# SFP.net
KiCad netlist of a schematic drawn in Altium Designer
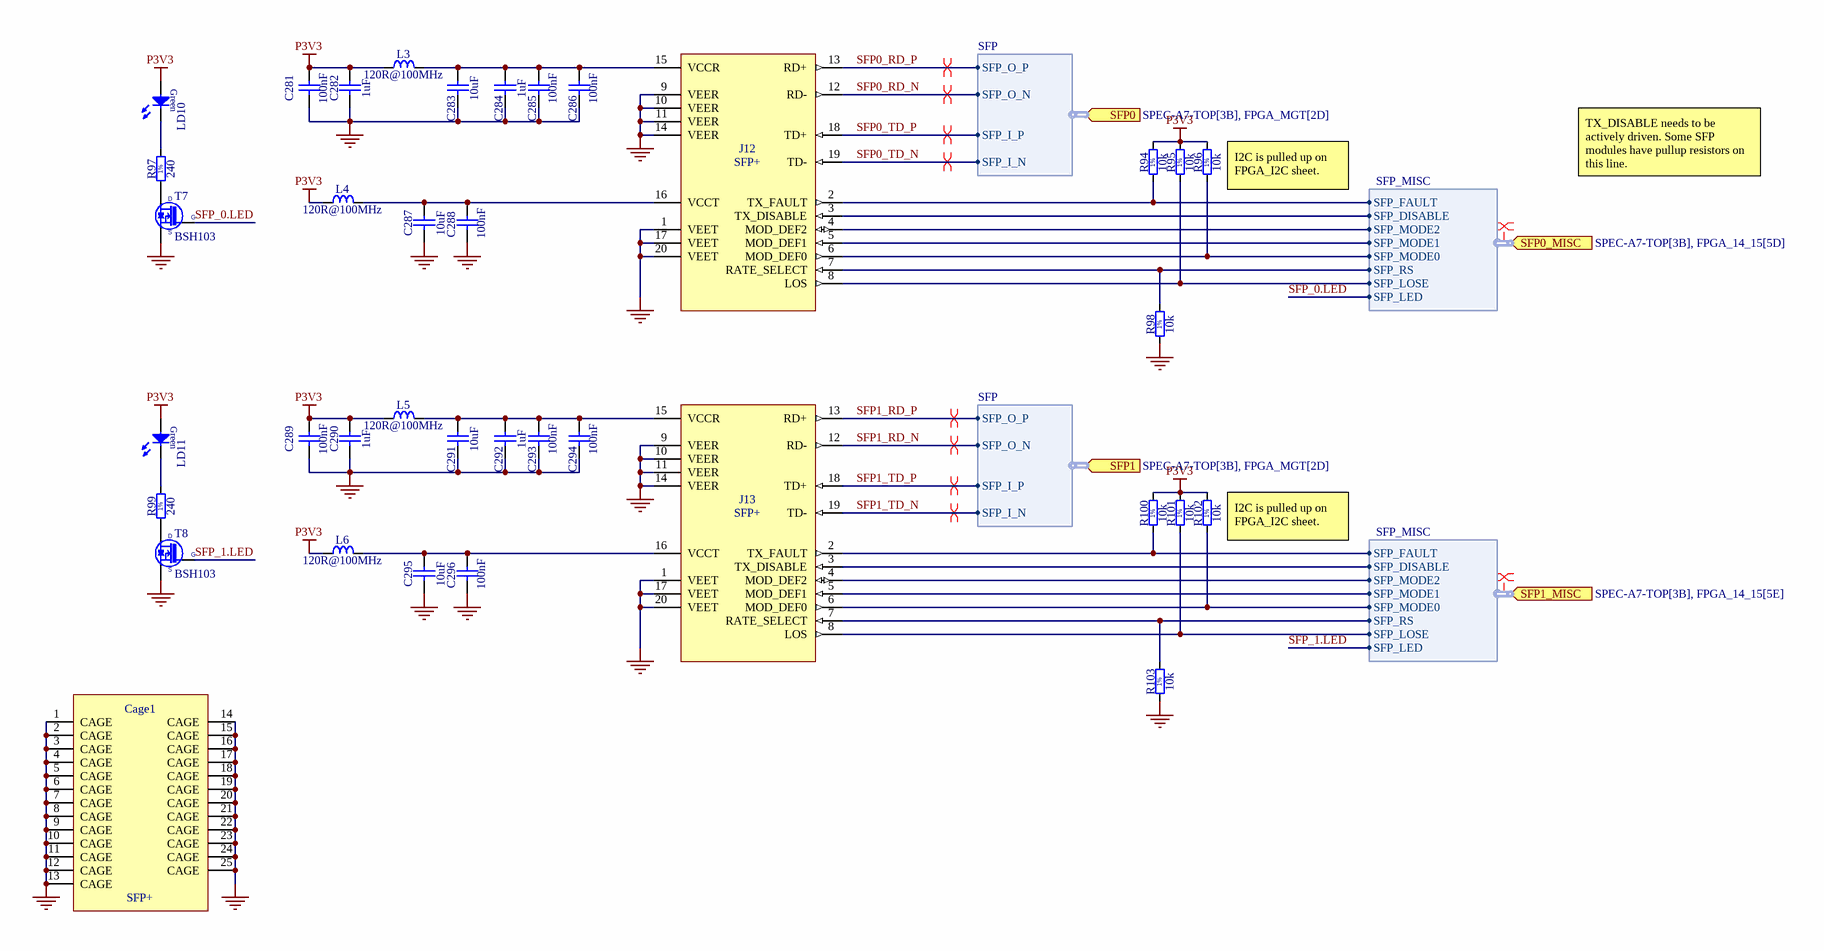
[diagram p0: SFP.SchDoc]

(export (version "E")
  (design (tool "Eeschema 10.0.6"))
  (components
    (comp (ref "C281")
      (value "100nF")
      (footprint "CAPC0603X33N")
      (description "Non-polarised capacitor")
      (fields
        (field (name "PART NUMBER") "CC0201_100NF_6.3V_10%_X5R")
        (field (name "VOLTAGE") "6.3V")
        (field (name "AUTHOR") "CERN DEM JLC")
      )
      (libsource (lib "Capacitors") (part "Capacitor - non polarized"))
    )
    (comp (ref "C282")
      (value "1uF")
      (footprint "CAPC1005X55N")
      (description "Non-polarised capacitor")
      (fields
        (field (name "PART NUMBER") "CC0402_1UF_16V_10%_X5R")
        (field (name "VOLTAGE") "16V")
        (field (name "AUTHOR") "CERN DEM JLC")
      )
      (libsource (lib "Capacitors") (part "Capacitor - non polarized"))
    )
    (comp (ref "C283")
      (value "10uF")
      (footprint "CAPC1608X80N")
      (description "Non-polarised capacitor")
      (fields
        (field (name "PART NUMBER") "CC0603_10UF_16V_20%_X5R")
        (field (name "VOLTAGE") "16V")
        (field (name "AUTHOR") "CERN DEM MR")
      )
      (libsource (lib "Capacitors") (part "Capacitor - non polarized"))
    )
    (comp (ref "C284")
      (value "1uF")
      (footprint "CAPC1005X55N")
      (description "Non-polarised capacitor")
      (fields
        (field (name "PART NUMBER") "CC0402_1UF_16V_10%_X5R")
        (field (name "VOLTAGE") "16V")
        (field (name "AUTHOR") "CERN DEM JLC")
      )
      (libsource (lib "Capacitors") (part "Capacitor - non polarized"))
    )
    (comp (ref "C285")
      (value "100nF")
      (footprint "CAPC0603X33N")
      (description "Non-polarised capacitor")
      (fields
        (field (name "PART NUMBER") "CC0201_100NF_6.3V_10%_X5R")
        (field (name "VOLTAGE") "6.3V")
        (field (name "AUTHOR") "CERN DEM JLC")
      )
      (libsource (lib "Capacitors") (part "Capacitor - non polarized"))
    )
    (comp (ref "C286")
      (value "100nF")
      (footprint "CAPC0603X33N")
      (description "Non-polarised capacitor")
      (fields
        (field (name "PART NUMBER") "CC0201_100NF_6.3V_10%_X5R")
        (field (name "VOLTAGE") "6.3V")
        (field (name "AUTHOR") "CERN DEM JLC")
      )
      (libsource (lib "Capacitors") (part "Capacitor - non polarized"))
    )
    (comp (ref "C287")
      (value "10uF")
      (footprint "CAPC1608X80N")
      (description "Non-polarised capacitor")
      (fields
        (field (name "PART NUMBER") "CC0603_10UF_16V_20%_X5R")
        (field (name "VOLTAGE") "16V")
        (field (name "AUTHOR") "CERN DEM MR")
      )
      (libsource (lib "Capacitors") (part "Capacitor - non polarized"))
    )
    (comp (ref "C288")
      (value "100nF")
      (footprint "CAPC0603X33N")
      (description "Non-polarised capacitor")
      (fields
        (field (name "PART NUMBER") "CC0201_100NF_6.3V_10%_X5R")
        (field (name "VOLTAGE") "6.3V")
        (field (name "AUTHOR") "CERN DEM JLC")
      )
      (libsource (lib "Capacitors") (part "Capacitor - non polarized"))
    )
    (comp (ref "C289")
      (value "100nF")
      (footprint "CAPC0603X33N")
      (description "Non-polarised capacitor")
      (fields
        (field (name "PART NUMBER") "CC0201_100NF_6.3V_10%_X5R")
        (field (name "VOLTAGE") "6.3V")
        (field (name "AUTHOR") "CERN DEM JLC")
      )
      (libsource (lib "Capacitors") (part "Capacitor - non polarized"))
    )
    (comp (ref "C290")
      (value "1uF")
      (footprint "CAPC1005X55N")
      (description "Non-polarised capacitor")
      (fields
        (field (name "PART NUMBER") "CC0402_1UF_16V_10%_X5R")
        (field (name "VOLTAGE") "16V")
        (field (name "AUTHOR") "CERN DEM JLC")
      )
      (libsource (lib "Capacitors") (part "Capacitor - non polarized"))
    )
    (comp (ref "C291")
      (value "10uF")
      (footprint "CAPC1608X80N")
      (description "Non-polarised capacitor")
      (fields
        (field (name "PART NUMBER") "CC0603_10UF_16V_20%_X5R")
        (field (name "VOLTAGE") "16V")
        (field (name "AUTHOR") "CERN DEM MR")
      )
      (libsource (lib "Capacitors") (part "Capacitor - non polarized"))
    )
    (comp (ref "C292")
      (value "1uF")
      (footprint "CAPC1005X55N")
      (description "Non-polarised capacitor")
      (fields
        (field (name "PART NUMBER") "CC0402_1UF_16V_10%_X5R")
        (field (name "VOLTAGE") "16V")
        (field (name "AUTHOR") "CERN DEM JLC")
      )
      (libsource (lib "Capacitors") (part "Capacitor - non polarized"))
    )
    (comp (ref "C293")
      (value "100nF")
      (footprint "CAPC0603X33N")
      (description "Non-polarised capacitor")
      (fields
        (field (name "PART NUMBER") "CC0201_100NF_6.3V_10%_X5R")
        (field (name "VOLTAGE") "6.3V")
        (field (name "AUTHOR") "CERN DEM JLC")
      )
      (libsource (lib "Capacitors") (part "Capacitor - non polarized"))
    )
    (comp (ref "C294")
      (value "100nF")
      (footprint "CAPC0603X33N")
      (description "Non-polarised capacitor")
      (fields
        (field (name "PART NUMBER") "CC0201_100NF_6.3V_10%_X5R")
        (field (name "VOLTAGE") "6.3V")
        (field (name "AUTHOR") "CERN DEM JLC")
      )
      (libsource (lib "Capacitors") (part "Capacitor - non polarized"))
    )
    (comp (ref "C295")
      (value "10uF")
      (footprint "CAPC1608X80N")
      (description "Non-polarised capacitor")
      (fields
        (field (name "PART NUMBER") "CC0603_10UF_16V_20%_X5R")
        (field (name "VOLTAGE") "16V")
        (field (name "AUTHOR") "CERN DEM MR")
      )
      (libsource (lib "Capacitors") (part "Capacitor - non polarized"))
    )
    (comp (ref "C296")
      (value "100nF")
      (footprint "CAPC0603X33N")
      (description "Non-polarised capacitor")
      (fields
        (field (name "PART NUMBER") "CC0201_100NF_6.3V_10%_X5R")
        (field (name "VOLTAGE") "6.3V")
        (field (name "AUTHOR") "CERN DEM JLC")
      )
      (libsource (lib "Capacitors") (part "Capacitor - non polarized"))
    )
    (comp (ref "Cage1")
      (value "SFP+")
      (footprint "TYCO_2007263-1")
      (description "SFP 1x2 Cage (25Pins)")
      (fields
        (field (name "PART NUMBER") "TYCO_2007263-1")
        (field (name "MANUFACTURER") "TYCO ELECTRONICS")
        (field (name "AUTHOR") "CERN DEM JLC")
      )
      (libsource (lib "Connectors") (part "SFP 1x2 Cage (25Pins)"))
    )
    (comp (ref "J12")
      (value "SFP+")
      (footprint "MOLEX_74441-0001")
      (description "20 Position SFP  Connector (Small Form-factor Pluggable)")
      (fields
        (field (name "PART NUMBER") "MOLEX_74441-0001")
        (field (name "MANUFACTURER") "MOLEX")
        (field (name "AUTHOR") "CERN DEM MR")
      )
      (libsource (lib "Connectors") (part "SFPx1"))
    )
    (comp (ref "J13")
      (value "SFP+")
      (footprint "MOLEX_74441-0001")
      (description "20 Position SFP  Connector (Small Form-factor Pluggable)")
      (fields
        (field (name "PART NUMBER") "MOLEX_74441-0001")
        (field (name "MANUFACTURER") "MOLEX")
        (field (name "AUTHOR") "CERN DEM MR")
      )
      (libsource (lib "Connectors") (part "SFPx1"))
    )
    (comp (ref "L3")
      (value "120R@100MHz")
      (footprint "INDC1608X65N")
      (description "Inductor")
      (fields
        (field (name "PART NUMBER") "IND0603_MURATA_BLM18SG121TN1D")
        (field (name "POWER") "3A")
        (field (name "AUTHOR") "CERN DEM JLC")
      )
      (libsource (lib "Inductors & Transformers") (part "Inductor"))
    )
    (comp (ref "L4")
      (value "120R@100MHz")
      (footprint "INDC1608X65N")
      (description "Inductor")
      (fields
        (field (name "PART NUMBER") "IND0603_MURATA_BLM18SG121TN1D")
        (field (name "POWER") "3A")
        (field (name "AUTHOR") "CERN DEM JLC")
      )
      (libsource (lib "Inductors & Transformers") (part "Inductor"))
    )
    (comp (ref "L5")
      (value "120R@100MHz")
      (footprint "INDC1608X65N")
      (description "Inductor")
      (fields
        (field (name "PART NUMBER") "IND0603_MURATA_BLM18SG121TN1D")
        (field (name "POWER") "3A")
        (field (name "AUTHOR") "CERN DEM JLC")
      )
      (libsource (lib "Inductors & Transformers") (part "Inductor"))
    )
    (comp (ref "L6")
      (value "120R@100MHz")
      (footprint "INDC1608X65N")
      (description "Inductor")
      (fields
        (field (name "PART NUMBER") "IND0603_MURATA_BLM18SG121TN1D")
        (field (name "POWER") "3A")
        (field (name "AUTHOR") "CERN DEM JLC")
      )
      (libsource (lib "Inductors & Transformers") (part "Inductor"))
    )
    (comp (ref "LD10")
      (value "Green")
      (footprint "LED_AVAGO_HSME-C120")
      (description "LED Green 1C 2A")
      (fields
        (field (name "PART NUMBER") "LED_AVAGO_HSME-C120")
        (field (name "MANUFACTURER") "AVAGO TECHNOLOGIES")
        (field (name "AUTHOR") "CERN DEM JMW")
      )
      (libsource (lib "ICs And Semiconductors") (part "LED Green 1C 2A"))
    )
    (comp (ref "LD11")
      (value "Green")
      (footprint "LED_AVAGO_HSME-C120")
      (description "LED Green 1C 2A")
      (fields
        (field (name "PART NUMBER") "LED_AVAGO_HSME-C120")
        (field (name "MANUFACTURER") "AVAGO TECHNOLOGIES")
        (field (name "AUTHOR") "CERN DEM JMW")
      )
      (libsource (lib "ICs And Semiconductors") (part "LED Green 1C 2A"))
    )
    (comp (ref "R94")
      (value "10k")
      (footprint "RESC1005X40N")
      (description "Resistor - 1%")
      (fields
        (field (name "PART NUMBER") "R0402_10K_1%_0.0625W_100PPM")
        (field (name "POWER") "0.0625W")
        (field (name "AUTHOR") "CERN DEM JLC")
      )
      (libsource (lib "Resistors") (part "Resistor - 1%"))
    )
    (comp (ref "R95")
      (value "10k")
      (footprint "RESC1005X40N")
      (description "Resistor - 1%")
      (fields
        (field (name "PART NUMBER") "R0402_10K_1%_0.0625W_100PPM")
        (field (name "POWER") "0.0625W")
        (field (name "AUTHOR") "CERN DEM JLC")
      )
      (libsource (lib "Resistors") (part "Resistor - 1%"))
    )
    (comp (ref "R96")
      (value "10k")
      (footprint "RESC1005X40N")
      (description "Resistor - 1%")
      (fields
        (field (name "PART NUMBER") "R0402_10K_1%_0.0625W_100PPM")
        (field (name "POWER") "0.0625W")
        (field (name "AUTHOR") "CERN DEM JLC")
      )
      (libsource (lib "Resistors") (part "Resistor - 1%"))
    )
    (comp (ref "R97")
      (value "240")
      (footprint "RESC1005X40N")
      (description "Resistor - 1%")
      (fields
        (field (name "PART NUMBER") "R0402_240R_1%_0.0625W_100PPM")
        (field (name "POWER") "0.0625W")
        (field (name "AUTHOR") "CERN DEM JLC")
      )
      (libsource (lib "Resistors") (part "Resistor - 1%"))
    )
    (comp (ref "R98")
      (value "10k")
      (footprint "RESC1005X40N")
      (description "Resistor - 1%")
      (fields
        (field (name "PART NUMBER") "R0402_10K_1%_0.0625W_100PPM")
        (field (name "POWER") "0.0625W")
        (field (name "AUTHOR") "CERN DEM JLC")
      )
      (libsource (lib "Resistors") (part "Resistor - 1%"))
    )
    (comp (ref "R99")
      (value "240")
      (footprint "RESC1005X40N")
      (description "Resistor - 1%")
      (fields
        (field (name "PART NUMBER") "R0402_240R_1%_0.0625W_100PPM")
        (field (name "POWER") "0.0625W")
        (field (name "AUTHOR") "CERN DEM JLC")
      )
      (libsource (lib "Resistors") (part "Resistor - 1%"))
    )
    (comp (ref "R100")
      (value "10k")
      (footprint "RESC1005X40N")
      (description "Resistor - 1%")
      (fields
        (field (name "PART NUMBER") "R0402_10K_1%_0.0625W_100PPM")
        (field (name "POWER") "0.0625W")
        (field (name "AUTHOR") "CERN DEM JLC")
      )
      (libsource (lib "Resistors") (part "Resistor - 1%"))
    )
    (comp (ref "R101")
      (value "10k")
      (footprint "RESC1005X40N")
      (description "Resistor - 1%")
      (fields
        (field (name "PART NUMBER") "R0402_10K_1%_0.0625W_100PPM")
        (field (name "POWER") "0.0625W")
        (field (name "AUTHOR") "CERN DEM JLC")
      )
      (libsource (lib "Resistors") (part "Resistor - 1%"))
    )
    (comp (ref "R102")
      (value "10k")
      (footprint "RESC1005X40N")
      (description "Resistor - 1%")
      (fields
        (field (name "PART NUMBER") "R0402_10K_1%_0.0625W_100PPM")
        (field (name "POWER") "0.0625W")
        (field (name "AUTHOR") "CERN DEM JLC")
      )
      (libsource (lib "Resistors") (part "Resistor - 1%"))
    )
    (comp (ref "R103")
      (value "10k")
      (footprint "RESC1005X40N")
      (description "Resistor - 1%")
      (fields
        (field (name "PART NUMBER") "R0402_10K_1%_0.0625W_100PPM")
        (field (name "POWER") "0.0625W")
        (field (name "AUTHOR") "CERN DEM JLC")
      )
      (libsource (lib "Resistors") (part "Resistor - 1%"))
    )
    (comp (ref "T7")
      (value "BSH103")
      (footprint "SOT95P230X110-3N")
      (description "N-CHANNEL MOSFET WITH DIODE")
      (fields (field (name "MANUFACTURER") "NEXPERIA") (field (name "AUTHOR") "CERN DEM JLC"))
      (libsource (lib "ICs And Semiconductors") (part "N-MOSFET-D 1G 2S 3D"))
    )
    (comp (ref "T8")
      (value "BSH103")
      (footprint "SOT95P230X110-3N")
      (description "N-CHANNEL MOSFET WITH DIODE")
      (fields (field (name "MANUFACTURER") "NEXPERIA") (field (name "AUTHOR") "CERN DEM JLC"))
      (libsource (lib "ICs And Semiconductors") (part "N-MOSFET-D 1G 2S 3D"))
    )
  )
  (nets
    (net (code "3") (name "/SFP0_RD_N") (class "Default")
      (node (ref "J12") (pin "12") (pinfunction "RD-_12") (pintype "output"))
    )
    (net (code "4") (name "/SFP0_RD_P") (class "Default")
      (node (ref "J12") (pin "13") (pinfunction "RD+_13") (pintype "output"))
    )
    (net (code "5") (name "/SFP0_TD_N") (class "Default")
      (node (ref "J12") (pin "19") (pinfunction "TD-_19") (pintype "input"))
    )
    (net (code "6") (name "/SFP0_TD_P") (class "Default")
      (node (ref "J12") (pin "18") (pinfunction "TD+_18") (pintype "input"))
    )
    (net (code "7") (name "/SFP1_RD_N") (class "Default")
      (node (ref "J13") (pin "12") (pinfunction "RD-_12") (pintype "output"))
    )
    (net (code "8") (name "/SFP1_RD_P") (class "Default")
      (node (ref "J13") (pin "13") (pinfunction "RD+_13") (pintype "output"))
    )
    (net (code "9") (name "/SFP1_TD_N") (class "Default")
      (node (ref "J13") (pin "19") (pinfunction "TD-_19") (pintype "input"))
    )
    (net (code "10") (name "/SFP1_TD_P") (class "Default")
      (node (ref "J13") (pin "18") (pinfunction "TD+_18") (pintype "input"))
    )
    (net (code "11") (name "/SFP_0.LED") (class "Default")
      (node (ref "T7") (pin "1") (pinfunction "G_1") (pintype "passive"))
    )
    (net (code "12") (name "/SFP_1.LED") (class "Default")
      (node (ref "T8") (pin "1") (pinfunction "G_1") (pintype "passive"))
    )
    (net (code "15") (name "GND") (class "Default")
      (node (ref "C281") (pin "1") (pinfunction "1_1") (pintype "passive"))
      (node (ref "C282") (pin "1") (pinfunction "1_1") (pintype "passive"))
      (node (ref "C283") (pin "1") (pinfunction "1_1") (pintype "passive"))
      (node (ref "C284") (pin "1") (pinfunction "1_1") (pintype "passive"))
      (node (ref "C285") (pin "1") (pinfunction "1_1") (pintype "passive"))
      (node (ref "C286") (pin "1") (pinfunction "1_1") (pintype "passive"))
      (node (ref "C287") (pin "1") (pinfunction "1_1") (pintype "passive"))
      (node (ref "C288") (pin "1") (pinfunction "1_1") (pintype "passive"))
      (node (ref "C289") (pin "1") (pinfunction "1_1") (pintype "passive"))
      (node (ref "C290") (pin "1") (pinfunction "1_1") (pintype "passive"))
      (node (ref "C291") (pin "1") (pinfunction "1_1") (pintype "passive"))
      (node (ref "C292") (pin "1") (pinfunction "1_1") (pintype "passive"))
      (node (ref "C293") (pin "1") (pinfunction "1_1") (pintype "passive"))
      (node (ref "C294") (pin "1") (pinfunction "1_1") (pintype "passive"))
      (node (ref "C295") (pin "1") (pinfunction "1_1") (pintype "passive"))
      (node (ref "C296") (pin "1") (pinfunction "1_1") (pintype "passive"))
      (node (ref "Cage1") (pin "1") (pinfunction "CAGE_1") (pintype "power_in"))
      (node (ref "Cage1") (pin "10") (pinfunction "CAGE_10") (pintype "power_in"))
      (node (ref "Cage1") (pin "11") (pinfunction "CAGE_11") (pintype "power_in"))
      (node (ref "Cage1") (pin "12") (pinfunction "CAGE_12") (pintype "power_in"))
      (node (ref "Cage1") (pin "13") (pinfunction "CAGE_13") (pintype "power_in"))
      (node (ref "Cage1") (pin "14") (pinfunction "CAGE_14") (pintype "power_in"))
      (node (ref "Cage1") (pin "15") (pinfunction "CAGE_15") (pintype "power_in"))
      (node (ref "Cage1") (pin "16") (pinfunction "CAGE_16") (pintype "power_in"))
      (node (ref "Cage1") (pin "17") (pinfunction "CAGE_17") (pintype "power_in"))
      (node (ref "Cage1") (pin "18") (pinfunction "CAGE_18") (pintype "power_in"))
      (node (ref "Cage1") (pin "19") (pinfunction "CAGE_19") (pintype "power_in"))
      (node (ref "Cage1") (pin "2") (pinfunction "CAGE_2") (pintype "power_in"))
      (node (ref "Cage1") (pin "20") (pinfunction "CAGE_20") (pintype "power_in"))
      (node (ref "Cage1") (pin "21") (pinfunction "CAGE_21") (pintype "power_in"))
      (node (ref "Cage1") (pin "22") (pinfunction "CAGE_22") (pintype "power_in"))
      (node (ref "Cage1") (pin "23") (pinfunction "CAGE_23") (pintype "power_in"))
      (node (ref "Cage1") (pin "24") (pinfunction "CAGE_24") (pintype "power_in"))
      (node (ref "Cage1") (pin "25") (pinfunction "CAGE_25") (pintype "power_in"))
      (node (ref "Cage1") (pin "3") (pinfunction "CAGE_3") (pintype "power_in"))
      (node (ref "Cage1") (pin "4") (pinfunction "CAGE_4") (pintype "power_in"))
      (node (ref "Cage1") (pin "5") (pinfunction "CAGE_5") (pintype "power_in"))
      (node (ref "Cage1") (pin "6") (pinfunction "CAGE_6") (pintype "power_in"))
      (node (ref "Cage1") (pin "7") (pinfunction "CAGE_7") (pintype "power_in"))
      (node (ref "Cage1") (pin "8") (pinfunction "CAGE_8") (pintype "power_in"))
      (node (ref "Cage1") (pin "9") (pinfunction "CAGE_9") (pintype "power_in"))
      (node (ref "J12") (pin "1") (pinfunction "VEET_1") (pintype "power_in"))
      (node (ref "J12") (pin "10") (pinfunction "VEER_10") (pintype "power_in"))
      (node (ref "J12") (pin "11") (pinfunction "VEER_11") (pintype "power_in"))
      (node (ref "J12") (pin "14") (pinfunction "VEER_14") (pintype "power_in"))
      (node (ref "J12") (pin "17") (pinfunction "VEET_17") (pintype "power_in"))
      (node (ref "J12") (pin "20") (pinfunction "VEET_20") (pintype "power_in"))
      (node (ref "J12") (pin "9") (pinfunction "VEER_9") (pintype "power_in"))
      (node (ref "J13") (pin "1") (pinfunction "VEET_1") (pintype "power_in"))
      (node (ref "J13") (pin "10") (pinfunction "VEER_10") (pintype "power_in"))
      (node (ref "J13") (pin "11") (pinfunction "VEER_11") (pintype "power_in"))
      (node (ref "J13") (pin "14") (pinfunction "VEER_14") (pintype "power_in"))
      (node (ref "J13") (pin "17") (pinfunction "VEET_17") (pintype "power_in"))
      (node (ref "J13") (pin "20") (pinfunction "VEET_20") (pintype "power_in"))
      (node (ref "J13") (pin "9") (pinfunction "VEER_9") (pintype "power_in"))
      (node (ref "R103") (pin "1") (pinfunction "1_1") (pintype "passive"))
      (node (ref "R98") (pin "1") (pinfunction "1_1") (pintype "passive"))
      (node (ref "T7") (pin "2") (pinfunction "S_2") (pintype "passive"))
      (node (ref "T8") (pin "2") (pinfunction "S_2") (pintype "passive"))
    )
    (net (code "16") (name "Net-(J12-LOS)") (class "Default")
      (node (ref "J12") (pin "8") (pinfunction "LOS_8") (pintype "output"))
      (node (ref "R95") (pin "1") (pinfunction "1_1") (pintype "passive"))
    )
    (net (code "17") (name "Net-(J12-MOD_DEF0)") (class "Default")
      (node (ref "J12") (pin "6") (pinfunction "MOD_DEF0_6") (pintype "output"))
      (node (ref "R96") (pin "1") (pinfunction "1_1") (pintype "passive"))
    )
    (net (code "18") (name "Net-(J12-RATE_SELECT)") (class "Default")
      (node (ref "J12") (pin "7") (pinfunction "RATE_SELECT_7") (pintype "input"))
      (node (ref "R98") (pin "2") (pinfunction "2_2") (pintype "passive"))
    )
    (net (code "19") (name "Net-(J12-TX_FAULT)") (class "Default")
      (node (ref "J12") (pin "2") (pinfunction "TX_FAULT_2") (pintype "output"))
      (node (ref "R94") (pin "1") (pinfunction "1_1") (pintype "passive"))
    )
    (net (code "20") (name "Net-(J12-VCCR)") (class "Default")
      (node (ref "C283") (pin "2") (pinfunction "2_2") (pintype "passive"))
      (node (ref "C284") (pin "2") (pinfunction "2_2") (pintype "passive"))
      (node (ref "C285") (pin "2") (pinfunction "2_2") (pintype "passive"))
      (node (ref "C286") (pin "2") (pinfunction "2_2") (pintype "passive"))
      (node (ref "J12") (pin "15") (pinfunction "VCCR_15") (pintype "power_in"))
      (node (ref "L3") (pin "2") (pinfunction "2_2") (pintype "passive"))
    )
    (net (code "21") (name "Net-(J12-VCCT)") (class "Default")
      (node (ref "C287") (pin "2") (pinfunction "2_2") (pintype "passive"))
      (node (ref "C288") (pin "2") (pinfunction "2_2") (pintype "passive"))
      (node (ref "J12") (pin "16") (pinfunction "VCCT_16") (pintype "power_in"))
      (node (ref "L4") (pin "2") (pinfunction "2_2") (pintype "passive"))
    )
    (net (code "22") (name "Net-(J13-LOS)") (class "Default")
      (node (ref "J13") (pin "8") (pinfunction "LOS_8") (pintype "output"))
      (node (ref "R101") (pin "1") (pinfunction "1_1") (pintype "passive"))
    )
    (net (code "23") (name "Net-(J13-MOD_DEF0)") (class "Default")
      (node (ref "J13") (pin "6") (pinfunction "MOD_DEF0_6") (pintype "output"))
      (node (ref "R102") (pin "1") (pinfunction "1_1") (pintype "passive"))
    )
    (net (code "24") (name "Net-(J13-RATE_SELECT)") (class "Default")
      (node (ref "J13") (pin "7") (pinfunction "RATE_SELECT_7") (pintype "input"))
      (node (ref "R103") (pin "2") (pinfunction "2_2") (pintype "passive"))
    )
    (net (code "25") (name "Net-(J13-TX_FAULT)") (class "Default")
      (node (ref "J13") (pin "2") (pinfunction "TX_FAULT_2") (pintype "output"))
      (node (ref "R100") (pin "1") (pinfunction "1_1") (pintype "passive"))
    )
    (net (code "26") (name "Net-(J13-VCCR)") (class "Default")
      (node (ref "C291") (pin "2") (pinfunction "2_2") (pintype "passive"))
      (node (ref "C292") (pin "2") (pinfunction "2_2") (pintype "passive"))
      (node (ref "C293") (pin "2") (pinfunction "2_2") (pintype "passive"))
      (node (ref "C294") (pin "2") (pinfunction "2_2") (pintype "passive"))
      (node (ref "J13") (pin "15") (pinfunction "VCCR_15") (pintype "power_in"))
      (node (ref "L5") (pin "2") (pinfunction "2_2") (pintype "passive"))
    )
    (net (code "27") (name "Net-(J13-VCCT)") (class "Default")
      (node (ref "C295") (pin "2") (pinfunction "2_2") (pintype "passive"))
      (node (ref "C296") (pin "2") (pinfunction "2_2") (pintype "passive"))
      (node (ref "J13") (pin "16") (pinfunction "VCCT_16") (pintype "power_in"))
      (node (ref "L6") (pin "2") (pinfunction "2_2") (pintype "passive"))
    )
    (net (code "28") (name "Net-(LD10-C)") (class "Default")
      (node (ref "LD10") (pin "1") (pinfunction "C_1") (pintype "passive"))
      (node (ref "R97") (pin "2") (pinfunction "2_2") (pintype "passive"))
    )
    (net (code "29") (name "Net-(LD11-C)") (class "Default")
      (node (ref "LD11") (pin "1") (pinfunction "C_1") (pintype "passive"))
      (node (ref "R99") (pin "2") (pinfunction "2_2") (pintype "passive"))
    )
    (net (code "30") (name "Net-(T7-D)") (class "Default")
      (node (ref "R97") (pin "1") (pinfunction "1_1") (pintype "passive"))
      (node (ref "T7") (pin "3") (pinfunction "D_3") (pintype "passive"))
    )
    (net (code "31") (name "Net-(T8-D)") (class "Default")
      (node (ref "R99") (pin "1") (pinfunction "1_1") (pintype "passive"))
      (node (ref "T8") (pin "3") (pinfunction "D_3") (pintype "passive"))
    )
    (net (code "32") (name "P3V3") (class "Default")
      (node (ref "C281") (pin "2") (pinfunction "2_2") (pintype "passive"))
      (node (ref "C282") (pin "2") (pinfunction "2_2") (pintype "passive"))
      (node (ref "C289") (pin "2") (pinfunction "2_2") (pintype "passive"))
      (node (ref "C290") (pin "2") (pinfunction "2_2") (pintype "passive"))
      (node (ref "L3") (pin "1") (pinfunction "1_1") (pintype "passive"))
      (node (ref "L4") (pin "1") (pinfunction "1_1") (pintype "passive"))
      (node (ref "L5") (pin "1") (pinfunction "1_1") (pintype "passive"))
      (node (ref "L6") (pin "1") (pinfunction "1_1") (pintype "passive"))
      (node (ref "LD10") (pin "2") (pinfunction "A_2") (pintype "passive"))
      (node (ref "LD11") (pin "2") (pinfunction "A_2") (pintype "passive"))
      (node (ref "R100") (pin "2") (pinfunction "2_2") (pintype "passive"))
      (node (ref "R101") (pin "2") (pinfunction "2_2") (pintype "passive"))
      (node (ref "R102") (pin "2") (pinfunction "2_2") (pintype "passive"))
      (node (ref "R94") (pin "2") (pinfunction "2_2") (pintype "passive"))
      (node (ref "R95") (pin "2") (pinfunction "2_2") (pintype "passive"))
      (node (ref "R96") (pin "2") (pinfunction "2_2") (pintype "passive"))
    )
    (net (code "33") (name "unconnected-(J12-MOD_DEF1-Pad5)") (class "Default")
      (node (ref "J12") (pin "5") (pinfunction "MOD_DEF1_5") (pintype "input"))
    )
    (net (code "34") (name "unconnected-(J12-MOD_DEF2-Pad4)") (class "Default")
      (node (ref "J12") (pin "4") (pinfunction "MOD_DEF2_4") (pintype "bidirectional"))
    )
    (net (code "35") (name "unconnected-(J12-TX_DISABLE-Pad3)") (class "Default")
      (node (ref "J12") (pin "3") (pinfunction "TX_DISABLE_3") (pintype "input"))
    )
    (net (code "36") (name "unconnected-(J13-MOD_DEF1-Pad5)") (class "Default")
      (node (ref "J13") (pin "5") (pinfunction "MOD_DEF1_5") (pintype "input"))
    )
    (net (code "37") (name "unconnected-(J13-MOD_DEF2-Pad4)") (class "Default")
      (node (ref "J13") (pin "4") (pinfunction "MOD_DEF2_4") (pintype "bidirectional"))
    )
    (net (code "38") (name "unconnected-(J13-TX_DISABLE-Pad3)") (class "Default")
      (node (ref "J13") (pin "3") (pinfunction "TX_DISABLE_3") (pintype "input"))
    )
  )
)
